# STM32G0_Breakout_Board.net
KiCad netlist of a schematic drawn in EAGLE
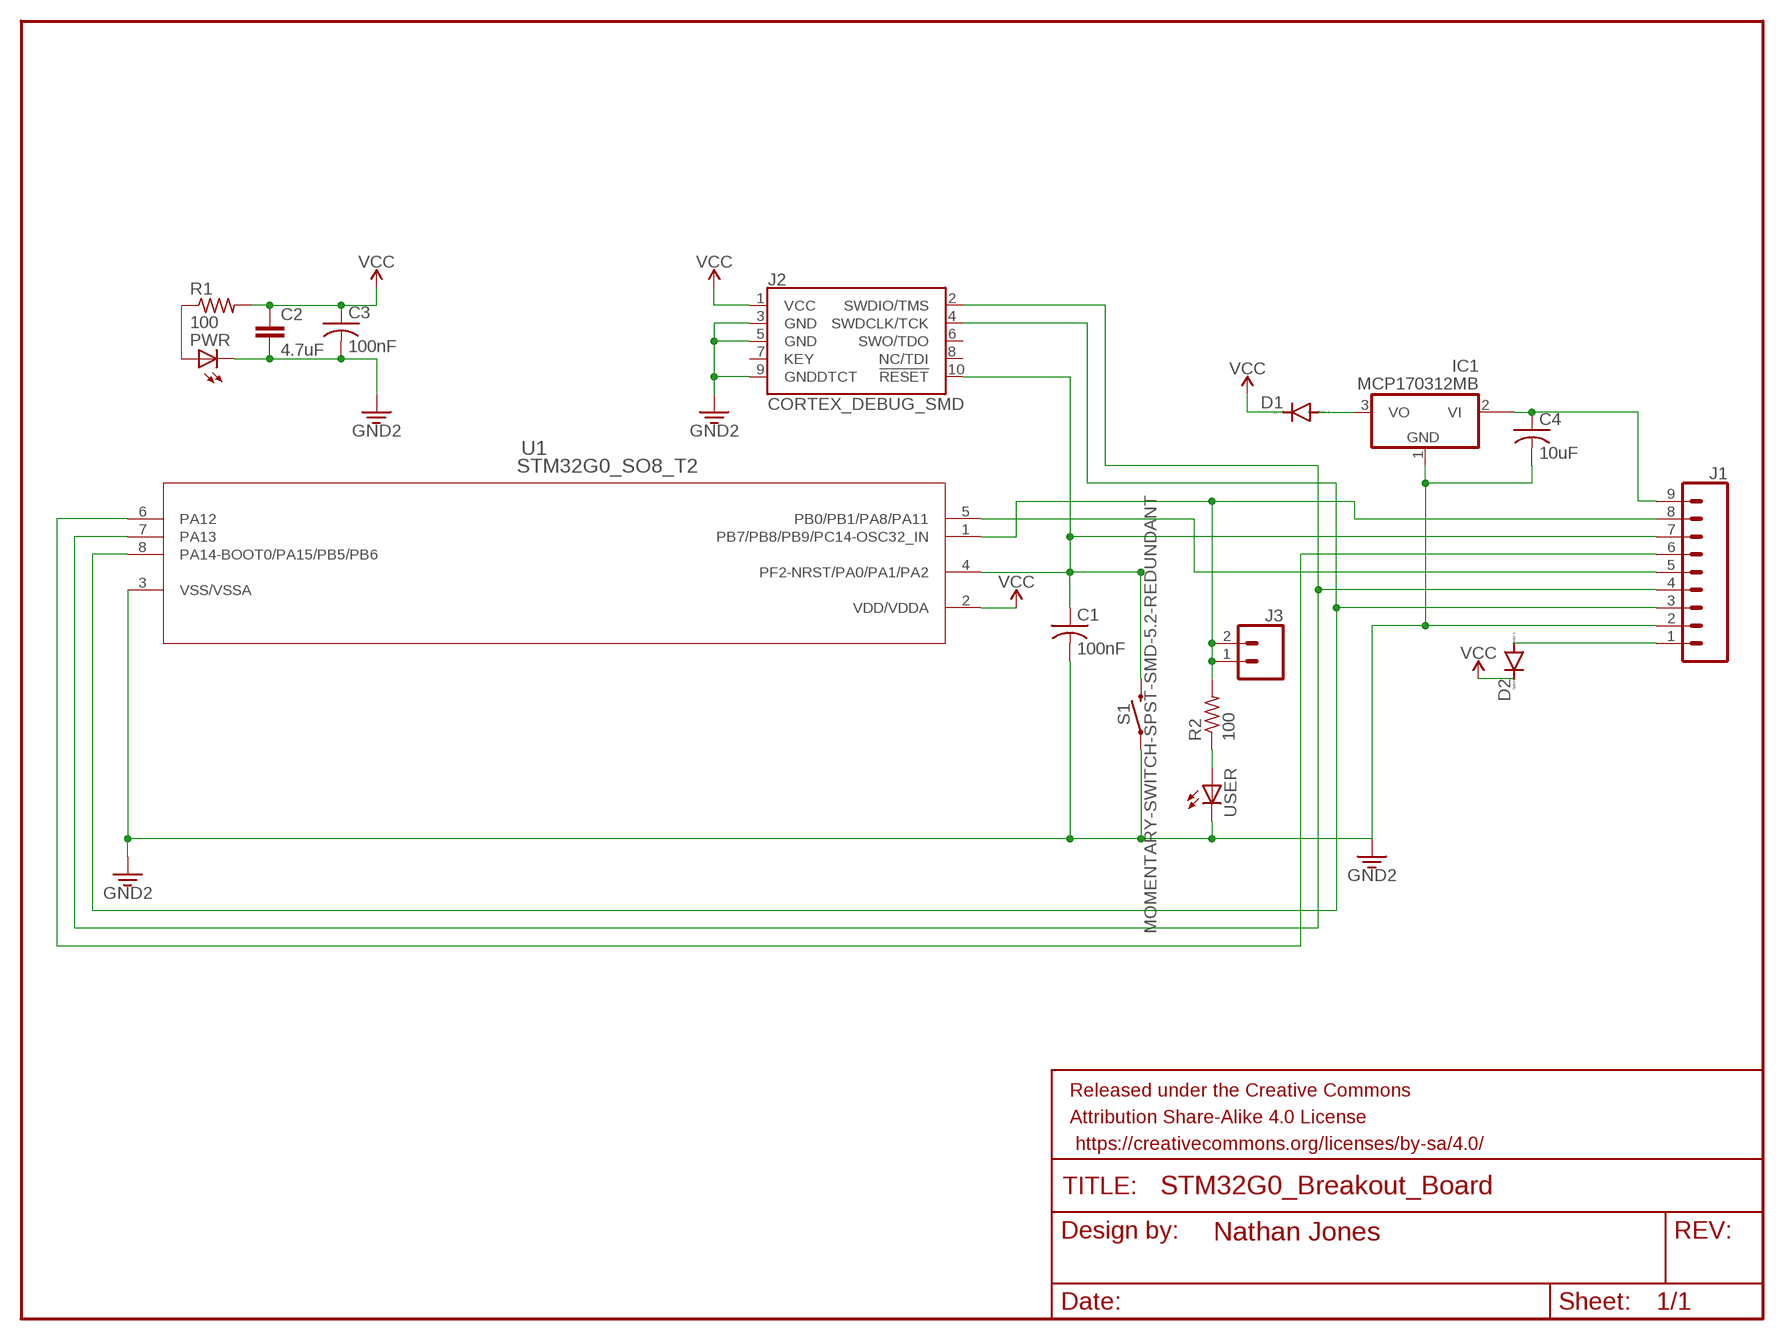
[diagram p0: schematic, sheet 1]

(export (version "E")
  (design (tool "Eeschema 10.0.6"))
  (components
    (comp (ref "C1")
      (value "100nF")
      (footprint "eagle-import:C1206")
      (libsource (lib "eagle-import") (part "C-USC1206"))
    )
    (comp (ref "C2")
      (value "4.7uF")
      (footprint "eagle-import:1206")
      (libsource (lib "eagle-import") (part "4.7UF-1206-16V-(+80/-20%)"))
    )
    (comp (ref "C3")
      (value "100nF")
      (footprint "eagle-import:C1206")
      (libsource (lib "eagle-import") (part "C-USC1206"))
    )
    (comp (ref "C4")
      (value "10uF")
      (footprint "eagle-import:C1206")
      (libsource (lib "eagle-import") (part "C-USC1206"))
    )
    (comp (ref "D1")
      (value "DIODE-DO-214AC")
      (footprint "eagle-import:DO-214AC")
      (libsource (lib "eagle-import") (part "DIODE-DO-214AC"))
    )
    (comp (ref "D2")
      (value "DIODE-DO-214AC")
      (footprint "eagle-import:DO-214AC")
      (libsource (lib "eagle-import") (part "DIODE-DO-214AC"))
    )
    (comp (ref "FRAME1")
      (value "FRAME-LETTERNO_PACKAGE")
      (footprint "eagle-import:DUMMY")
      (fields (field (name "DESIGNER") "Nathan Jones") (field (name "DESIGNER_1") "Nathan Jones"))
      (libsource (lib "eagle-import") (part "FRAME-LETTERNO_PACKAGE"))
    )
    (comp (ref "IC1")
      (value "MCP170312MB")
      (footprint "eagle-import:SOT89")
      (libsource (lib "eagle-import") (part "MCP1703MB12"))
    )
    (comp (ref "J1")
      (value "CONN_09LONGPADS")
      (footprint "eagle-import:1X09_LONGPADS")
      (libsource (lib "eagle-import") (part "CONN_09LONGPADS"))
    )
    (comp (ref "J2")
      (value "CORTEX_DEBUG_SMD")
      (footprint "eagle-import:SAMTECH_FTSH-105-01")
      (libsource (lib "eagle-import") (part "CORTEX_DEBUG_SMD"))
    )
    (comp (ref "J3")
      (value "CONN_02PTH3")
      (footprint "eagle-import:1X02_LONGPADS")
      (libsource (lib "eagle-import") (part "CONN_02PTH3"))
    )
    (comp (ref "PWR")
      (value "LEDCHIP-LED0805")
      (footprint "eagle-import:CHIP-LED0805")
      (libsource (lib "eagle-import") (part "LEDCHIP-LED0805"))
    )
    (comp (ref "R1")
      (value "100")
      (footprint "eagle-import:R1206")
      (libsource (lib "eagle-import") (part "R-US_R1206"))
    )
    (comp (ref "R2")
      (value "100")
      (footprint "eagle-import:R1206")
      (libsource (lib "eagle-import") (part "R-US_R1206"))
    )
    (comp (ref "S1")
      (value "MOMENTARY-SWITCH-SPST-SMD-5.2-REDUNDANT")
      (footprint "eagle-import:TACTILE_SWITCH_SMD_5.2MM")
      (libsource (lib "eagle-import") (part "MOMENTARY-SWITCH-SPST-SMD-5.2-REDUNDANT"))
    )
    (comp (ref "U1")
      (value "STM32G0_SO8_T2")
      (footprint "eagle-import:SO-8")
      (libsource (lib "eagle-import") (part "STM32G0_SO8_T2"))
    )
    (comp (ref "USER")
      (value "LEDCHIP-LED0805")
      (footprint "eagle-import:CHIP-LED0805")
      (libsource (lib "eagle-import") (part "LEDCHIP-LED0805"))
    )
  )
  (nets
    (net (code "1") (name "GND2") (class "Default")
      (node (ref "C1") (pin "2") (pinfunction "2_2") (pintype "passive"))
      (node (ref "C2") (pin "2") (pinfunction "2_2") (pintype "passive"))
      (node (ref "C3") (pin "2") (pinfunction "2_2") (pintype "passive"))
      (node (ref "C4") (pin "2") (pinfunction "2_2") (pintype "passive"))
      (node (ref "IC1") (pin "1") (pinfunction "GND_1") (pintype "passive"))
      (node (ref "J1") (pin "2") (pinfunction "2_2") (pintype "passive"))
      (node (ref "J2") (pin "3") (pinfunction "GND_3") (pintype "bidirectional"))
      (node (ref "J2") (pin "5") (pinfunction "GND_5") (pintype "bidirectional"))
      (node (ref "J2") (pin "9") (pinfunction "GNDDTCT_9") (pintype "bidirectional"))
      (node (ref "PWR") (pin "C") (pinfunction "C_C") (pintype "passive"))
      (node (ref "S1") (pin "1") (pinfunction "1_1") (pintype "passive"))
      (node (ref "S1") (pin "2") (pinfunction "1_2") (pintype "passive"))
      (node (ref "U1") (pin "3") (pinfunction "VSS/VSSA_3") (pintype "power_in"))
      (node (ref "USER") (pin "C") (pinfunction "C_C") (pintype "passive"))
    )
    (net (code "2") (name "Net-(D2-PadA)") (class "Default")
      (node (ref "D2") (pin "A") (pinfunction "A_A") (pintype "passive"))
      (node (ref "J1") (pin "1") (pinfunction "1_1") (pintype "passive"))
    )
    (net (code "3") (name "Net-(IC1-VI1)") (class "Default")
      (node (ref "C4") (pin "1") (pinfunction "1_1") (pintype "passive"))
      (node (ref "IC1") (pin "2@1") (pinfunction "VI1_2@1") (pintype "input"))
      (node (ref "J1") (pin "9") (pinfunction "9_9") (pintype "passive"))
    )
    (net (code "4") (name "Net-(IC1-VO)") (class "Default")
      (node (ref "D1") (pin "A") (pinfunction "A_A") (pintype "passive"))
      (node (ref "IC1") (pin "3") (pinfunction "VO_3") (pintype "passive"))
    )
    (net (code "5") (name "Net-(J2-SWDCLK{slash}TCK)") (class "Default")
      (node (ref "J1") (pin "3") (pinfunction "3_3") (pintype "passive"))
      (node (ref "J2") (pin "4") (pinfunction "SWDCLK/TCK_4") (pintype "bidirectional"))
      (node (ref "U1") (pin "8") (pinfunction "PA14-BOOT0/PA15/PB5/PB6_8") (pintype "bidirectional"))
    )
    (net (code "6") (name "Net-(J2-SWDIO{slash}TMS)") (class "Default")
      (node (ref "J1") (pin "4") (pinfunction "4_4") (pintype "passive"))
      (node (ref "J2") (pin "2") (pinfunction "SWDIO/TMS_2") (pintype "bidirectional"))
      (node (ref "U1") (pin "7") (pinfunction "PA13_7") (pintype "bidirectional"))
    )
    (net (code "7") (name "Net-(J2-~{RESET})") (class "Default")
      (node (ref "C1") (pin "1") (pinfunction "1_1") (pintype "passive"))
      (node (ref "J1") (pin "7") (pinfunction "7_7") (pintype "passive"))
      (node (ref "J2") (pin "10") (pinfunction "~{RESET}_10") (pintype "bidirectional"))
      (node (ref "S1") (pin "3") (pinfunction "2_3") (pintype "passive"))
      (node (ref "S1") (pin "4") (pinfunction "2_4") (pintype "passive"))
      (node (ref "U1") (pin "4") (pinfunction "PF2-NRST/PA0/PA1/PA2_4") (pintype "bidirectional"))
    )
    (net (code "8") (name "Net-(PWR-PadA)") (class "Default")
      (node (ref "PWR") (pin "A") (pinfunction "A_A") (pintype "passive"))
      (node (ref "R1") (pin "1") (pinfunction "1_1") (pintype "passive"))
    )
    (net (code "9") (name "Net-(R2-Pad1)") (class "Default")
      (node (ref "R2") (pin "1") (pinfunction "1_1") (pintype "passive"))
      (node (ref "USER") (pin "A") (pinfunction "A_A") (pintype "passive"))
    )
    (net (code "10") (name "Net-(U1-PA12)") (class "Default")
      (node (ref "J1") (pin "6") (pinfunction "6_6") (pintype "passive"))
      (node (ref "U1") (pin "6") (pinfunction "PA12_6") (pintype "bidirectional"))
    )
    (net (code "11") (name "Net-(U1-PB0{slash}PB1{slash}PA8{slash}PA11)") (class "Default")
      (node (ref "J1") (pin "5") (pinfunction "5_5") (pintype "passive"))
      (node (ref "U1") (pin "5") (pinfunction "PB0/PB1/PA8/PA11_5") (pintype "bidirectional"))
    )
    (net (code "12") (name "Net-(U1-PB7{slash}PB8{slash}PB9{slash}PC14-OSC32_IN)") (class "Default")
      (node (ref "J1") (pin "8") (pinfunction "8_8") (pintype "passive"))
      (node (ref "J3") (pin "1") (pinfunction "1_1") (pintype "passive"))
      (node (ref "J3") (pin "2") (pinfunction "2_2") (pintype "passive"))
      (node (ref "R2") (pin "2") (pinfunction "2_2") (pintype "passive"))
      (node (ref "U1") (pin "1") (pinfunction "PB7/PB8/PB9/PC14-OSC32_IN_1") (pintype "bidirectional"))
    )
    (net (code "13") (name "VCC") (class "Default")
      (node (ref "C2") (pin "1") (pinfunction "1_1") (pintype "passive"))
      (node (ref "C3") (pin "1") (pinfunction "1_1") (pintype "passive"))
      (node (ref "D1") (pin "C") (pinfunction "C_C") (pintype "passive"))
      (node (ref "D2") (pin "C") (pinfunction "C_C") (pintype "passive"))
      (node (ref "J2") (pin "1") (pinfunction "VCC_1") (pintype "bidirectional"))
      (node (ref "R1") (pin "2") (pinfunction "2_2") (pintype "passive"))
      (node (ref "U1") (pin "2") (pinfunction "VDD/VDDA_2") (pintype "power_in"))
    )
    (net (code "14") (name "unconnected-(IC1-VI-Pad2)") (class "Default")
      (node (ref "IC1") (pin "2") (pinfunction "VI_2") (pintype "input"))
    )
    (net (code "15") (name "unconnected-(J2-KEY-Pad7)") (class "Default")
      (node (ref "J2") (pin "7") (pinfunction "KEY_7") (pintype "bidirectional"))
    )
    (net (code "16") (name "unconnected-(J2-NC{slash}TDI-Pad8)") (class "Default")
      (node (ref "J2") (pin "8") (pinfunction "NC/TDI_8") (pintype "bidirectional"))
    )
    (net (code "17") (name "unconnected-(J2-SWO{slash}TDO-Pad6)") (class "Default")
      (node (ref "J2") (pin "6") (pinfunction "SWO/TDO_6") (pintype "bidirectional"))
    )
  )
)
